# temp-sensor.net
KiCad netlist of a schematic drawn in EAGLE
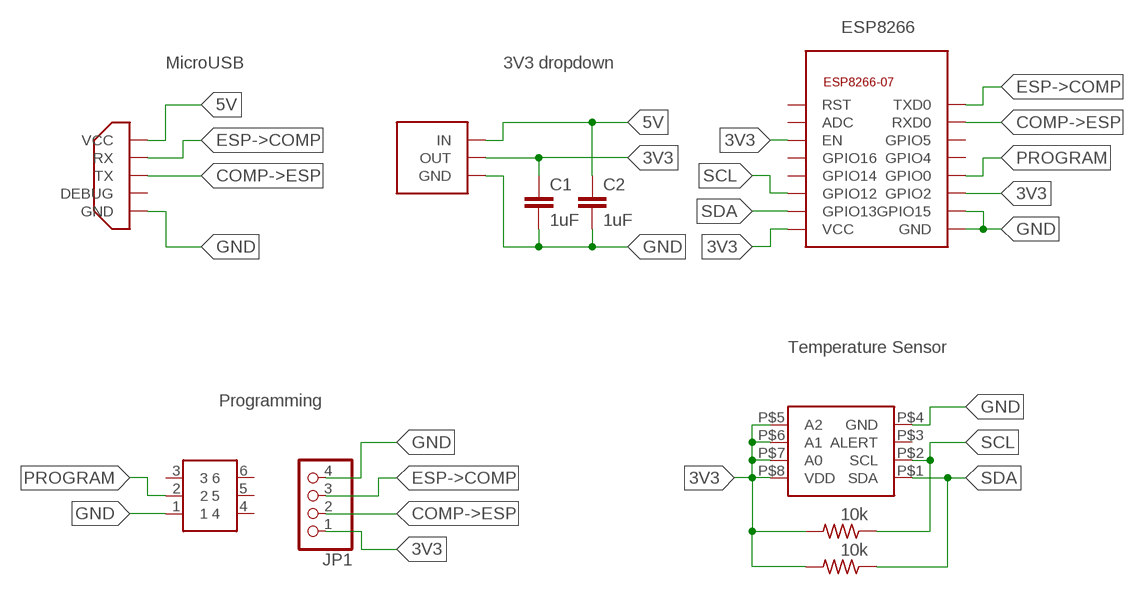
[diagram p0: schematic, sheet 1]

(export (version "E")
  (design (tool "Eeschema 10.0.6"))
  (components
    (comp (ref "C1")
      (value "1uF")
      (footprint "eagle-import:C0805")
      (libsource (lib "eagle-import") (part "C-EUC0805"))
    )
    (comp (ref "C2")
      (value "1uF")
      (footprint "eagle-import:C0805")
      (libsource (lib "eagle-import") (part "C-EUC0805"))
    )
    (comp (ref "JP1")
      (value "PINHD-1X4")
      (footprint "eagle-import:1X04")
      (libsource (lib "eagle-import") (part "PINHD-1X4"))
    )
    (comp (ref "R1")
      (value "10k")
      (footprint "eagle-import:M0805")
      (libsource (lib "eagle-import") (part "R-US_M0805"))
    )
    (comp (ref "R2")
      (value "10k")
      (footprint "eagle-import:M0805")
      (libsource (lib "eagle-import") (part "R-US_M0805"))
    )
    (comp (ref "U$1")
      (value "MCP9808")
      (footprint "eagle-import:MSOP-8")
      (libsource (lib "eagle-import") (part "MCP9808"))
    )
    (comp (ref "U$2")
      (value "ESP8266-12E-SMD")
      (footprint "eagle-import:ESP8266-12E-SMD")
      (libsource (lib "eagle-import") (part "ESP8266-12E-SMD"))
    )
    (comp (ref "U$3")
      (value "MICROUSB609-4613-1-ND")
      (footprint "eagle-import:MICROUSB")
      (libsource (lib "eagle-import") (part "MICROUSB609-4613-1-ND"))
    )
    (comp (ref "U$4")
      (value "AZ1117E")
      (footprint "eagle-import:SOT-223")
      (libsource (lib "eagle-import") (part "AZ1117E"))
    )
    (comp (ref "U$5")
      (value "AYZ0202AGRL")
      (footprint "eagle-import:AYZ0202AGRL")
      (libsource (lib "eagle-import") (part "AYZ0202AGRL"))
    )
  )
  (nets
    (net (code "1") (name "3V3") (class "Default")
      (node (ref "C1") (pin "1") (pinfunction "1_1") (pintype "passive"))
      (node (ref "JP1") (pin "1") (pinfunction "1_1") (pintype "passive"))
      (node (ref "R1") (pin "2") (pinfunction "2_2") (pintype "passive"))
      (node (ref "R2") (pin "2") (pinfunction "2_2") (pintype "passive"))
      (node (ref "U$1") (pin "P$5") (pinfunction "A2_P$5") (pintype "input"))
      (node (ref "U$1") (pin "P$6") (pinfunction "A1_P$6") (pintype "input"))
      (node (ref "U$1") (pin "P$7") (pinfunction "A0_P$7") (pintype "input"))
      (node (ref "U$1") (pin "P$8") (pinfunction "VDD_P$8") (pintype "power_in"))
      (node (ref "U$2") (pin "EN") (pinfunction "EN_EN") (pintype "input"))
      (node (ref "U$2") (pin "GPIO2") (pinfunction "GPIO2_GPIO2") (pintype "bidirectional"))
      (node (ref "U$2") (pin "VCC") (pinfunction "VCC_VCC") (pintype "power_in"))
      (node (ref "U$4") (pin "P$1") (pinfunction "OUT_P$1") (pintype "output"))
      (node (ref "U$4") (pin "P$2") (pinfunction "OUT_P$2") (pintype "output"))
    )
    (net (code "2") (name "5V") (class "Default")
      (node (ref "C2") (pin "1") (pinfunction "1_1") (pintype "passive"))
      (node (ref "U$3") (pin "VCC") (pinfunction "VCC_VCC") (pintype "power_in"))
      (node (ref "U$4") (pin "P$4") (pinfunction "IN_P$4") (pintype "input"))
    )
    (net (code "3") (name "COMP->ESP") (class "Default")
      (node (ref "JP1") (pin "2") (pinfunction "2_2") (pintype "passive"))
      (node (ref "U$2") (pin "RXD0") (pinfunction "RXD0_RXD0") (pintype "bidirectional"))
      (node (ref "U$3") (pin "TX") (pinfunction "TX_TX") (pintype "bidirectional"))
    )
    (net (code "4") (name "ESP->COMP") (class "Default")
      (node (ref "JP1") (pin "3") (pinfunction "3_3") (pintype "passive"))
      (node (ref "U$2") (pin "TXD0") (pinfunction "TXD0_TXD0") (pintype "bidirectional"))
      (node (ref "U$3") (pin "RX") (pinfunction "RX_RX") (pintype "bidirectional"))
    )
    (net (code "5") (name "GND") (class "Default")
      (node (ref "C1") (pin "2") (pinfunction "2_2") (pintype "passive"))
      (node (ref "C2") (pin "2") (pinfunction "2_2") (pintype "passive"))
      (node (ref "JP1") (pin "4") (pinfunction "4_4") (pintype "passive"))
      (node (ref "U$1") (pin "P$4") (pinfunction "GND_P$4") (pintype "power_in"))
      (node (ref "U$2") (pin "GND") (pinfunction "GND_GND") (pintype "power_in"))
      (node (ref "U$2") (pin "GPIO15") (pinfunction "GPIO15_GPIO15") (pintype "bidirectional"))
      (node (ref "U$3") (pin "GND") (pinfunction "GND_GND") (pintype "power_in"))
      (node (ref "U$4") (pin "P$3") (pinfunction "GND_P$3") (pintype "power_in"))
      (node (ref "U$5") (pin "1") (pinfunction "1_1") (pintype "bidirectional"))
    )
    (net (code "6") (name "PROGRAM") (class "Default")
      (node (ref "U$2") (pin "GPIO0") (pinfunction "GPIO0_GPIO0") (pintype "bidirectional"))
      (node (ref "U$5") (pin "2") (pinfunction "2_2") (pintype "bidirectional"))
    )
    (net (code "7") (name "SCL") (class "Default")
      (node (ref "R2") (pin "1") (pinfunction "1_1") (pintype "passive"))
      (node (ref "U$1") (pin "P$2") (pinfunction "SCL_P$2") (pintype "bidirectional"))
      (node (ref "U$2") (pin "GPIO12") (pinfunction "GPIO12_GPIO12") (pintype "bidirectional"))
    )
    (net (code "8") (name "SDA") (class "Default")
      (node (ref "R1") (pin "1") (pinfunction "1_1") (pintype "passive"))
      (node (ref "U$1") (pin "P$1") (pinfunction "SDA_P$1") (pintype "bidirectional"))
      (node (ref "U$2") (pin "GPIO13") (pinfunction "GPIO13_GPIO13") (pintype "bidirectional"))
    )
    (net (code "9") (name "unconnected-(U$1-ALERT-PadP$3)") (class "Default")
      (node (ref "U$1") (pin "P$3") (pinfunction "ALERT_P$3") (pintype "output"))
    )
    (net (code "10") (name "unconnected-(U$2-PadADC)") (class "Default")
      (node (ref "U$2") (pin "ADC") (pinfunction "ADC_ADC") (pintype "input"))
    )
    (net (code "11") (name "unconnected-(U$2-PadGPIO4)") (class "Default")
      (node (ref "U$2") (pin "GPIO4") (pinfunction "GPIO4_GPIO4") (pintype "bidirectional"))
    )
    (net (code "12") (name "unconnected-(U$2-PadGPIO5)") (class "Default")
      (node (ref "U$2") (pin "GPIO5") (pinfunction "GPIO5_GPIO5") (pintype "bidirectional"))
    )
    (net (code "13") (name "unconnected-(U$2-PadGPIO14)") (class "Default")
      (node (ref "U$2") (pin "GPIO14") (pinfunction "GPIO14_GPIO14") (pintype "bidirectional"))
    )
    (net (code "14") (name "unconnected-(U$2-PadGPIO16)") (class "Default")
      (node (ref "U$2") (pin "GPIO16") (pinfunction "GPIO16_GPIO16") (pintype "bidirectional"))
    )
    (net (code "15") (name "unconnected-(U$2-PadRST)") (class "Default")
      (node (ref "U$2") (pin "RST") (pinfunction "RST_RST") (pintype "input"))
    )
    (net (code "16") (name "unconnected-(U$3-PadDEBUG)") (class "Default")
      (node (ref "U$3") (pin "DEBUG") (pinfunction "DEBUG_DEBUG") (pintype "bidirectional"))
    )
    (net (code "17") (name "unconnected-(U$5-Pad3)") (class "Default")
      (node (ref "U$5") (pin "3") (pinfunction "3_3") (pintype "bidirectional"))
    )
    (net (code "18") (name "unconnected-(U$5-Pad4)") (class "Default")
      (node (ref "U$5") (pin "4") (pinfunction "4_4") (pintype "bidirectional"))
    )
    (net (code "19") (name "unconnected-(U$5-Pad5)") (class "Default")
      (node (ref "U$5") (pin "5") (pinfunction "5_5") (pintype "bidirectional"))
    )
    (net (code "20") (name "unconnected-(U$5-Pad6)") (class "Default")
      (node (ref "U$5") (pin "6") (pinfunction "6_6") (pintype "bidirectional"))
    )
  )
)
